# MCU.net
KiCad netlist of a schematic drawn in Altium Designer
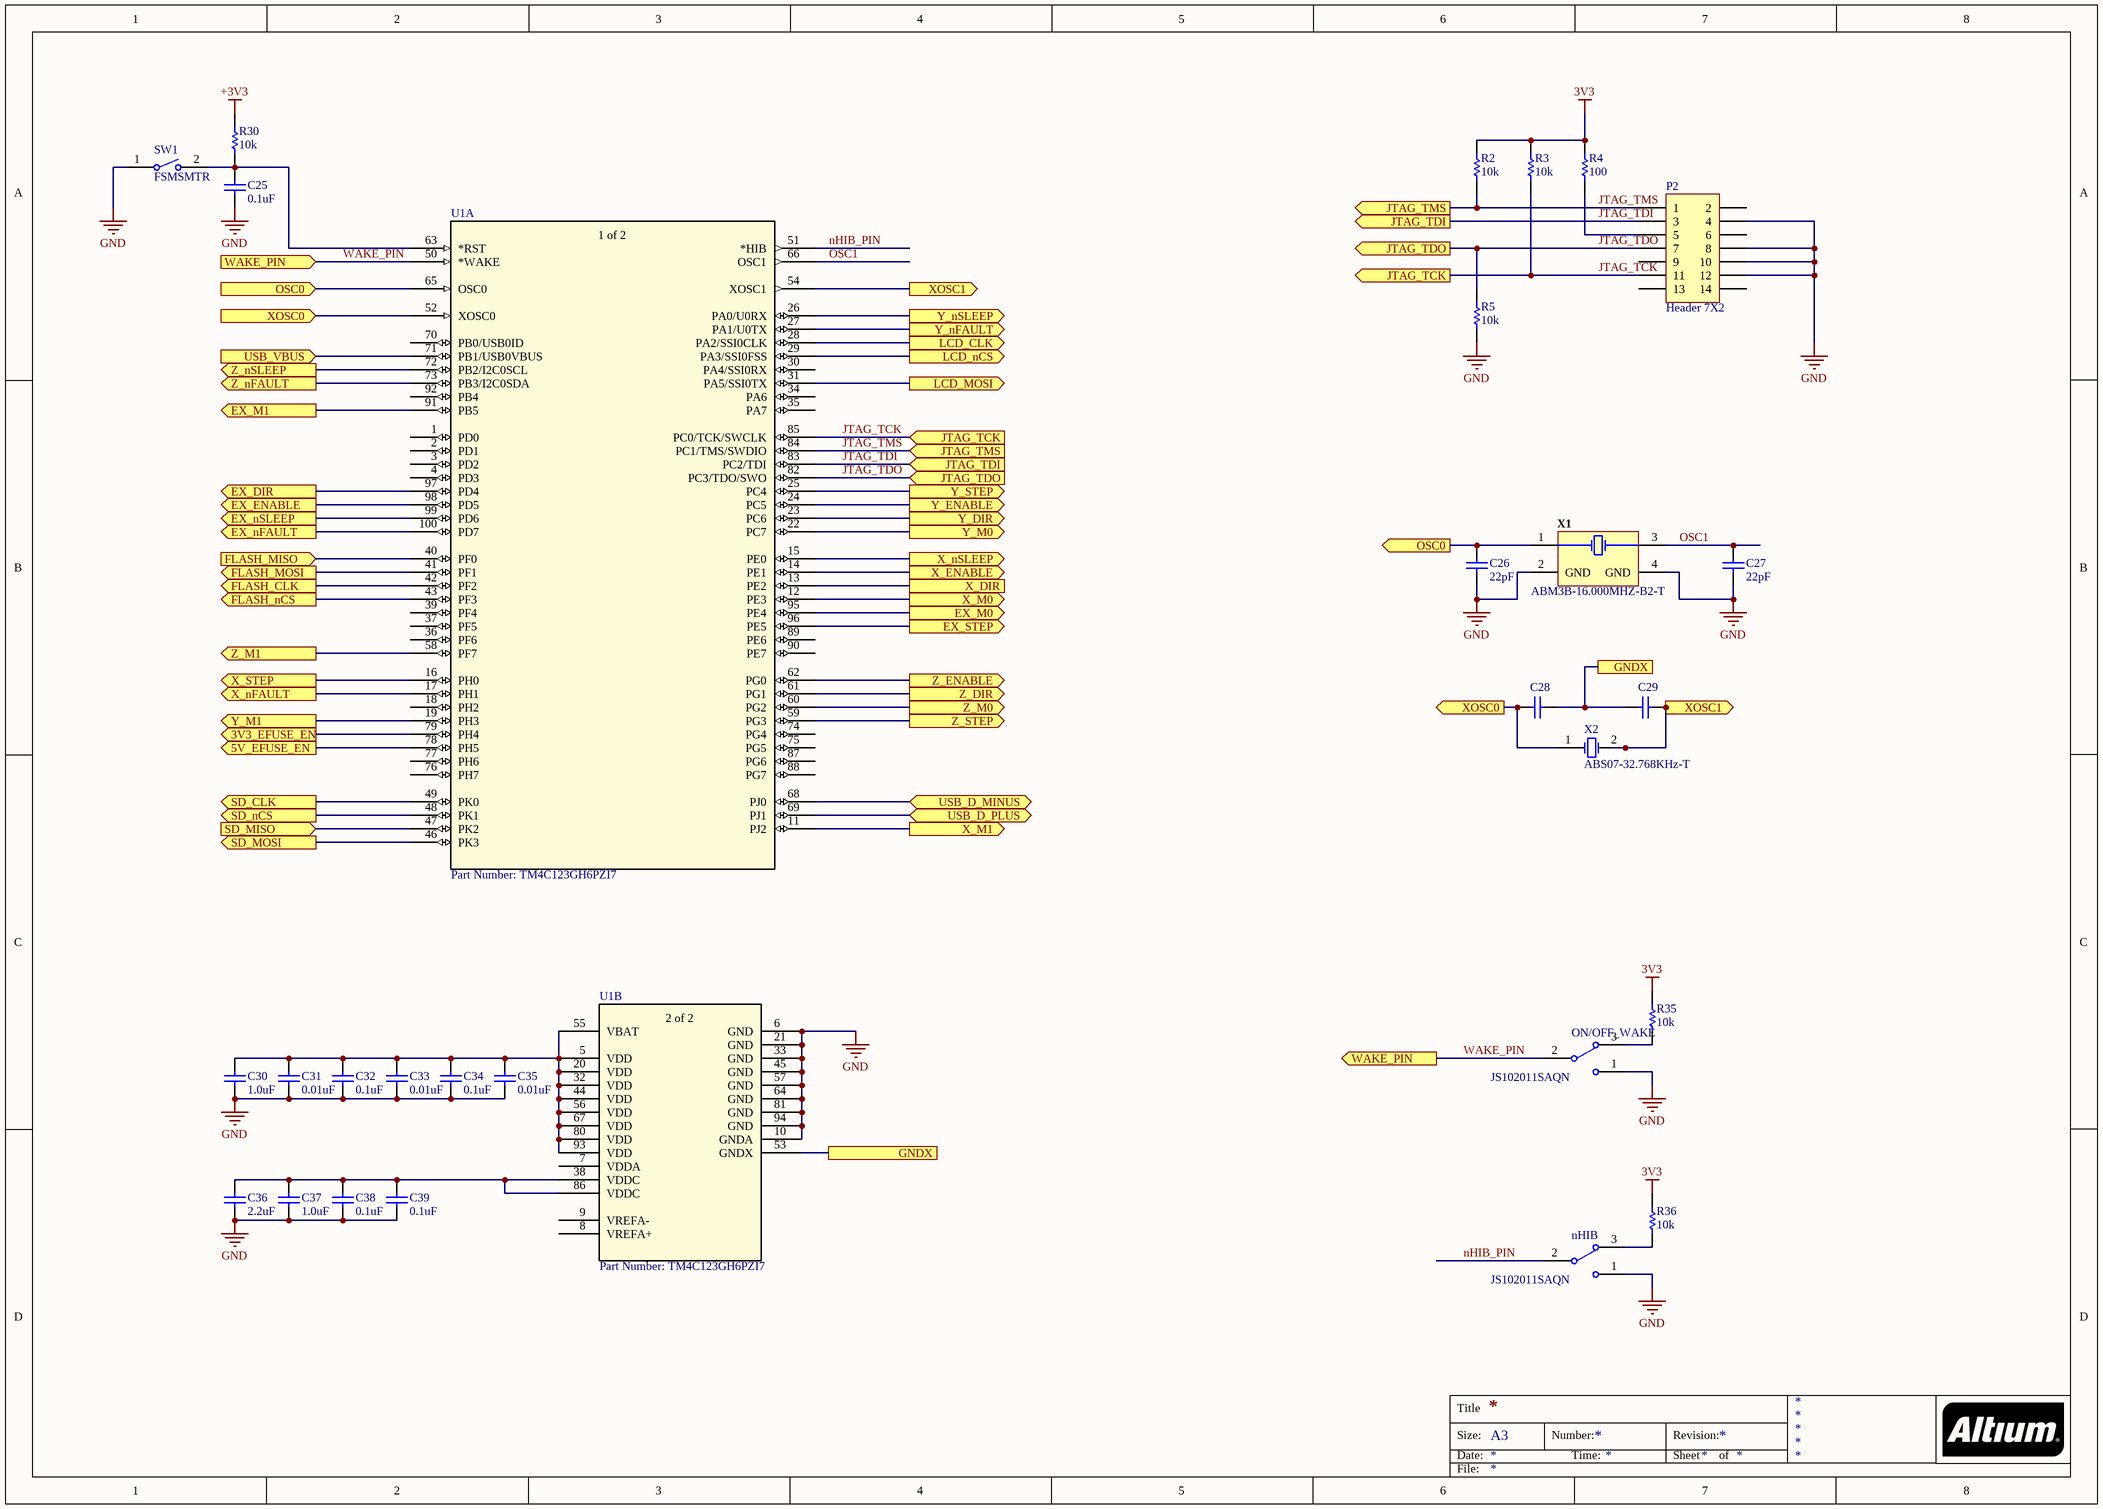
[diagram p0: MCU.SchDoc]

(export (version "E")
  (design (tool "Eeschema 10.0.6"))
  (components
    (comp (ref "C25")
      (value "0.1uF")
      (footprint "CAPC1608X90X35ML10T15")
      (description "Chip Capacitor, 0.1 uF, +/- 10%, 50 V, -55 to 125 degC, 0603 (1608 Metric), RoHS, Tape and Reel")
      (fields (field (name "TOLERANCE") "10%") (field (name "VOLTAGE") "50V"))
      (libsource (lib "Altium Content Vault") (part "CAP-NP-2"))
    )
    (comp (ref "C26")
      (value "22pF")
      (footprint "CAPC1608X90X35ML10T15")
      (fields (field (name "PART NUMBER") "GRM1885C1H120JA01D") (field (name "MANUFACTURER") "Murata"))
      (libsource (lib "Altium Content Vault") (part "CAP"))
    )
    (comp (ref "C27")
      (value "22pF")
      (footprint "CAPC1608X90X35ML10T15")
      (fields (field (name "PART NUMBER") "GRM1885C1H120JA01D") (field (name "MANUFACTURER") "Murata"))
      (libsource (lib "Altium Content Vault") (part "CAP"))
    )
    (comp (ref "C28")
      (value "GRM1885C1H120JA01D")
      (footprint "CAPC1608X90X35ML10T15")
      (fields (field (name "MANUFACTURER") "Murata"))
      (libsource (lib "Altium Content Vault") (part "CAP"))
    )
    (comp (ref "C29")
      (value "GRM1885C1H120JA01D")
      (footprint "CAPC1608X90X35ML10T15")
      (fields (field (name "MANUFACTURER") "Murata"))
      (libsource (lib "Altium Content Vault") (part "CAP"))
    )
    (comp (ref "C30")
      (value "1.0uF")
      (footprint "CAPC1608X60X35NL10T15")
      (fields (field (name "MANUFACTURER") "Murata") (field (name "PART NUMBER") "GRM185R61C105KE44J"))
      (libsource (lib "Altium Content Vault") (part "CAP"))
    )
    (comp (ref "C31")
      (value "0.01uF")
      (footprint "CAPC1608X87X35ML15T15")
      (fields (field (name "PART NUMBER") "C0603C103K4RACTU") (field (name "MANUFACTURER") "Kemet"))
      (libsource (lib "Altium Content Vault") (part "CAP"))
    )
    (comp (ref "C32")
      (value "0.1uF")
      (footprint "CAPC1608X90X35ML10T15")
      (description "Chip Capacitor, 0.1 uF, +/- 10%, 50 V, -55 to 125 degC, 0603 (1608 Metric), RoHS, Tape and Reel")
      (fields (field (name "TOLERANCE") "10%") (field (name "VOLTAGE") "50V"))
      (libsource (lib "Altium Content Vault") (part "CAP-NP-2"))
    )
    (comp (ref "C33")
      (value "0.01uF")
      (footprint "CAPC1608X87X35ML15T15")
      (fields (field (name "PART NUMBER") "C0603C103K4RACTU") (field (name "MANUFACTURER") "Kemet"))
      (libsource (lib "Altium Content Vault") (part "CAP"))
    )
    (comp (ref "C34")
      (value "0.1uF")
      (footprint "CAPC1608X90X35ML10T15")
      (description "Chip Capacitor, 0.1 uF, +/- 10%, 50 V, -55 to 125 degC, 0603 (1608 Metric), RoHS, Tape and Reel")
      (fields (field (name "TOLERANCE") "10%") (field (name "VOLTAGE") "50V"))
      (libsource (lib "Altium Content Vault") (part "CAP-NP-2"))
    )
    (comp (ref "C35")
      (value "0.01uF")
      (footprint "CAPC1608X87X35ML15T15")
      (fields (field (name "PART NUMBER") "C0603C103K4RACTU") (field (name "MANUFACTURER") "Kemet"))
      (libsource (lib "Altium Content Vault") (part "CAP"))
    )
    (comp (ref "C36")
      (value "2.2uF")
      (footprint "CAPC1608X90X35ML10T15")
      (fields (field (name "MANUFACTURER") "Murata") (field (name "PART NUMBER") "GRM188R71A225KE15D"))
      (libsource (lib "Altium Content Vault") (part "CAP"))
    )
    (comp (ref "C37")
      (value "1.0uF")
      (footprint "CAPC1608X60X35NL10T15")
      (fields (field (name "MANUFACTURER") "Murata") (field (name "PART NUMBER") "GRM185R61C105KE44J"))
      (libsource (lib "Altium Content Vault") (part "CAP"))
    )
    (comp (ref "C38")
      (value "0.1uF")
      (footprint "CAPC1608X90X35ML10T15")
      (description "Chip Capacitor, 0.1 uF, +/- 10%, 50 V, -55 to 125 degC, 0603 (1608 Metric), RoHS, Tape and Reel")
      (fields (field (name "TOLERANCE") "10%") (field (name "VOLTAGE") "50V"))
      (libsource (lib "Altium Content Vault") (part "CAP-NP-2"))
    )
    (comp (ref "C39")
      (value "0.1uF")
      (footprint "CAPC1608X90X35ML10T15")
      (description "Chip Capacitor, 0.1 uF, +/- 10%, 50 V, -55 to 125 degC, 0603 (1608 Metric), RoHS, Tape and Reel")
      (fields (field (name "TOLERANCE") "10%") (field (name "VOLTAGE") "50V"))
      (libsource (lib "Altium Content Vault") (part "CAP-NP-2"))
    )
    (comp (ref "nHIB")
      (value "JS102011SAQN")
      (footprint "CKCP-JS102011SAQN-3_V")
      (description "Sub-Miniature Slide Switch, SPDT, -40 to 85 degC, 3-Pin SMD, RoHS, Tape and Reel")
      (fields (field (name "MANUFACTURER") "C&K Components"))
      (libsource (lib "Altium Content Vault") (part "SW-SPDT-3"))
    )
    (comp (ref "ON/OFF_WAKE")
      (value "JS102011SAQN")
      (footprint "CKCP-JS102011SAQN-3_V")
      (description "Sub-Miniature Slide Switch, SPDT, -40 to 85 degC, 3-Pin SMD, RoHS, Tape and Reel")
      (fields (field (name "MANUFACTURER") "C&K Components"))
      (libsource (lib "Altium Content Vault") (part "SW-SPDT-3"))
    )
    (comp (ref "P2")
      (value "Header 7X2")
      (footprint "HDR2X7")
      (description "Header, 7-Pin, Dual row")
      (fields (field (name "PUBLISHER") "Altium Limited"))
      (libsource (lib "Miscellaneous Connectors") (part "Header 7X2"))
    )
    (comp (ref "R2")
      (value "10k")
      (footprint "RESC1608X55X30LL15T15")
      (fields (field (name "PART NUMBER") "ERJ-3EKF1002V") (field (name "MANUFACTURER") "Panasonic"))
      (libsource (lib "Altium Content Vault") (part "RES"))
    )
    (comp (ref "R3")
      (value "10k")
      (footprint "RESC1608X55X30LL15T15")
      (fields (field (name "PART NUMBER") "ERJ-3EKF1002V") (field (name "MANUFACTURER") "Panasonic"))
      (libsource (lib "Altium Content Vault") (part "RES"))
    )
    (comp (ref "R4")
      (value "100")
      (footprint "RESC1608X55X30LL15T15")
      (fields (field (name "PART NUMBER") "ERJ-3EKF1002V") (field (name "MANUFACTURER") "Panasonic"))
      (libsource (lib "Altium Content Vault") (part "RES"))
    )
    (comp (ref "R5")
      (value "10k")
      (footprint "RESC1608X55X30LL15T15")
      (fields (field (name "PART NUMBER") "ERJ-3EKF1002V") (field (name "MANUFACTURER") "Panasonic"))
      (libsource (lib "Altium Content Vault") (part "RES"))
    )
    (comp (ref "R30")
      (value "10k")
      (footprint "RESC1608X55X30LL15T15")
      (fields (field (name "PART NUMBER") "ERJ-3EKF1002V") (field (name "MANUFACTURER") "Panasonic"))
      (libsource (lib "Altium Content Vault") (part "RES"))
    )
    (comp (ref "R35")
      (value "10k")
      (footprint "RESC1608X55X30LL15T15")
      (fields (field (name "PART NUMBER") "ERJ-3EKF1002V") (field (name "MANUFACTURER") "Panasonic"))
      (libsource (lib "Altium Content Vault") (part "RES"))
    )
    (comp (ref "R36")
      (value "10k")
      (footprint "RESC1608X55X30LL15T15")
      (fields (field (name "PART NUMBER") "ERJ-3EKF1002V") (field (name "MANUFACTURER") "Panasonic"))
      (libsource (lib "Altium Content Vault") (part "RES"))
    )
    (comp (ref "SW1")
      (value "FSMSMTR")
      (footprint "TECO-FSMSMTR_V")
      (description "FSMSM Push Button Switch, 50 mA, -35 to 85 degC, 2-Pin SMD, RoHS, Tape and Reel")
      (fields (field (name "MANUFACTURER") "TE Connectivity"))
      (libsource (lib "Altium Content Vault") (part "SW-SPST-2_C"))
    )
    (comp (ref "U1")
      (value "Part Number: TM4C123GH6PZI7")
      (footprint "PZ100")
      (description "No Description Available")
      (fields
        (field (name "MANUFACTURER_PART_NUMBER") "TM4C123GH6PZI7")
        (field (name "COPYRIGHT") "Copyright (C) 2018 Accelerated Designs. All rights reserved")
      )
      (libsource (lib "Capstone_IFFF") (part "TM4C123GH6PZI7"))
    )
    (comp (ref "X1")
      (value "ABM3B-16.000MHZ-B2-T")
      (footprint "ABRA-ABM3B-4_V")
      (description "Ceramic SMD Crystal, 16 MHz, +/- 20 ppm, 50 Ohm, -20 to 70 degC, 4-Pin SMD, RoHS, Tape and Reel")
      (fields (field (name "TOLERANCE") "30%"))
      (libsource (lib "Altium Content Vault") (part "XTAL-1-3-4"))
    )
    (comp (ref "X2")
      (value "ABS07-32.768KHz-T")
      (footprint "ABRA-ABS07-2_V")
      (description "Crystal, 32.768 kHz, 12.5 pF, -40 to 85 degC, SMD Low Profile 3.2 x 1.5 x 0.9 mm, Tape and Reel")
      (fields (field (name "MANUFACTURER") "Abracon"))
      (libsource (lib "Altium Content Vault") (part "ABRA-ABS07-2"))
    )
  )
  (nets
    (net (code "1") (name "+3V3") (class "Default")
      (node (ref "R30") (pin "2") (pinfunction "2_2") (pintype "passive"))
    )
    (net (code "2") (name "/3V3_EFUSE_EN") (class "Default")
      (node (ref "U1") (pin "79") (pinfunction "PH4_79") (pintype "bidirectional"))
    )
    (net (code "3") (name "/5V_EFUSE_EN") (class "Default")
      (node (ref "U1") (pin "78") (pinfunction "PH5_78") (pintype "bidirectional"))
    )
    (net (code "4") (name "/EX_DIR") (class "Default")
      (node (ref "U1") (pin "97") (pinfunction "PD4_97") (pintype "bidirectional"))
    )
    (net (code "5") (name "/EX_ENABLE") (class "Default")
      (node (ref "U1") (pin "98") (pinfunction "PD5_98") (pintype "bidirectional"))
    )
    (net (code "6") (name "/EX_M0") (class "Default")
      (node (ref "U1") (pin "95") (pinfunction "PE4_95") (pintype "bidirectional"))
    )
    (net (code "7") (name "/EX_M1") (class "Default")
      (node (ref "U1") (pin "91") (pinfunction "PB5_91") (pintype "bidirectional"))
    )
    (net (code "8") (name "/EX_STEP") (class "Default")
      (node (ref "U1") (pin "96") (pinfunction "PE5_96") (pintype "bidirectional"))
    )
    (net (code "9") (name "/EX_nFAULT") (class "Default")
      (node (ref "U1") (pin "100") (pinfunction "PD7_100") (pintype "bidirectional"))
    )
    (net (code "10") (name "/EX_nSLEEP") (class "Default")
      (node (ref "U1") (pin "99") (pinfunction "PD6_99") (pintype "bidirectional"))
    )
    (net (code "11") (name "/FLASH_CLK") (class "Default")
      (node (ref "U1") (pin "42") (pinfunction "PF2_42") (pintype "bidirectional"))
    )
    (net (code "12") (name "/FLASH_MISO") (class "Default")
      (node (ref "U1") (pin "40") (pinfunction "PF0_40") (pintype "bidirectional"))
    )
    (net (code "13") (name "/FLASH_MOSI") (class "Default")
      (node (ref "U1") (pin "41") (pinfunction "PF1_41") (pintype "bidirectional"))
    )
    (net (code "14") (name "/FLASH_nCS") (class "Default")
      (node (ref "U1") (pin "43") (pinfunction "PF3_43") (pintype "bidirectional"))
    )
    (net (code "15") (name "/GNDX") (class "Default")
      (node (ref "C28") (pin "2") (pinfunction "2_2") (pintype "passive"))
      (node (ref "C29") (pin "1") (pinfunction "1_1") (pintype "passive"))
      (node (ref "U1") (pin "53") (pinfunction "GNDX_53") (pintype "power_in"))
    )
    (net (code "16") (name "/JTAG_TCK") (class "Default")
      (node (ref "P2") (pin "11") (pinfunction "11_11") (pintype "passive"))
      (node (ref "R3") (pin "1") (pinfunction "1_1") (pintype "passive"))
      (node (ref "U1") (pin "85") (pinfunction "PC0/TCK/SWCLK_85") (pintype "bidirectional"))
    )
    (net (code "17") (name "/JTAG_TDI") (class "Default")
      (node (ref "P2") (pin "3") (pinfunction "3_3") (pintype "passive"))
      (node (ref "U1") (pin "83") (pinfunction "PC2/TDI_83") (pintype "bidirectional"))
    )
    (net (code "18") (name "/JTAG_TDO") (class "Default")
      (node (ref "P2") (pin "7") (pinfunction "7_7") (pintype "passive"))
      (node (ref "R5") (pin "2") (pinfunction "2_2") (pintype "passive"))
      (node (ref "U1") (pin "82") (pinfunction "PC3/TDO/SWO_82") (pintype "bidirectional"))
    )
    (net (code "19") (name "/JTAG_TMS") (class "Default")
      (node (ref "P2") (pin "1") (pinfunction "1_1") (pintype "passive"))
      (node (ref "R2") (pin "1") (pinfunction "1_1") (pintype "passive"))
      (node (ref "U1") (pin "84") (pinfunction "PC1/TMS/SWDIO_84") (pintype "bidirectional"))
    )
    (net (code "20") (name "/LCD_CLK") (class "Default")
      (node (ref "U1") (pin "28") (pinfunction "PA2/SSI0CLK_28") (pintype "bidirectional"))
    )
    (net (code "21") (name "/LCD_MOSI") (class "Default")
      (node (ref "U1") (pin "31") (pinfunction "PA5/SSI0TX_31") (pintype "bidirectional"))
    )
    (net (code "22") (name "/LCD_nCS") (class "Default")
      (node (ref "U1") (pin "29") (pinfunction "PA3/SSI0FSS_29") (pintype "bidirectional"))
    )
    (net (code "23") (name "/OSC0") (class "Default")
      (node (ref "C26") (pin "2") (pinfunction "2_2") (pintype "passive"))
      (node (ref "U1") (pin "65") (pinfunction "OSC0_65") (pintype "input"))
      (node (ref "X1") (pin "1") (pinfunction "X1_1") (pintype "passive"))
    )
    (net (code "24") (name "/OSC1") (class "Default")
      (node (ref "C27") (pin "2") (pinfunction "2_2") (pintype "passive"))
      (node (ref "U1") (pin "66") (pinfunction "OSC1_66") (pintype "output"))
      (node (ref "X1") (pin "3") (pinfunction "X2_3") (pintype "passive"))
    )
    (net (code "25") (name "/SD_CLK") (class "Default")
      (node (ref "U1") (pin "49") (pinfunction "PK0_49") (pintype "bidirectional"))
    )
    (net (code "26") (name "/SD_MISO") (class "Default")
      (node (ref "U1") (pin "47") (pinfunction "PK2_47") (pintype "bidirectional"))
    )
    (net (code "27") (name "/SD_MOSI") (class "Default")
      (node (ref "U1") (pin "46") (pinfunction "PK3_46") (pintype "bidirectional"))
    )
    (net (code "28") (name "/SD_nCS") (class "Default")
      (node (ref "U1") (pin "48") (pinfunction "PK1_48") (pintype "bidirectional"))
    )
    (net (code "29") (name "/USB_D_MINUS") (class "Default")
      (node (ref "U1") (pin "68") (pinfunction "PJ0_68") (pintype "bidirectional"))
    )
    (net (code "30") (name "/USB_D_PLUS") (class "Default")
      (node (ref "U1") (pin "69") (pinfunction "PJ1_69") (pintype "bidirectional"))
    )
    (net (code "31") (name "/USB_VBUS") (class "Default")
      (node (ref "U1") (pin "71") (pinfunction "PB1/USB0VBUS_71") (pintype "bidirectional"))
    )
    (net (code "32") (name "/WAKE_PIN") (class "Default")
      (node (ref "ON/OFF_WAKE") (pin "2") (pinfunction "2_2") (pintype "passive"))
      (node (ref "U1") (pin "50") (pinfunction "*WAKE_50") (pintype "input"))
    )
    (net (code "33") (name "/XOSC0") (class "Default")
      (node (ref "C28") (pin "1") (pinfunction "1_1") (pintype "passive"))
      (node (ref "U1") (pin "52") (pinfunction "XOSC0_52") (pintype "input"))
      (node (ref "X2") (pin "1") (pinfunction "X1_1") (pintype "passive"))
    )
    (net (code "34") (name "/XOSC1") (class "Default")
      (node (ref "C29") (pin "2") (pinfunction "2_2") (pintype "passive"))
      (node (ref "U1") (pin "54") (pinfunction "XOSC1_54") (pintype "output"))
      (node (ref "X2") (pin "2") (pinfunction "X2_2") (pintype "passive"))
    )
    (net (code "35") (name "/X_DIR") (class "Default")
      (node (ref "U1") (pin "13") (pinfunction "PE2_13") (pintype "bidirectional"))
    )
    (net (code "36") (name "/X_ENABLE") (class "Default")
      (node (ref "U1") (pin "14") (pinfunction "PE1_14") (pintype "bidirectional"))
    )
    (net (code "37") (name "/X_M0") (class "Default")
      (node (ref "U1") (pin "12") (pinfunction "PE3_12") (pintype "bidirectional"))
    )
    (net (code "38") (name "/X_M1") (class "Default")
      (node (ref "U1") (pin "11") (pinfunction "PJ2_11") (pintype "bidirectional"))
    )
    (net (code "39") (name "/X_STEP") (class "Default")
      (node (ref "U1") (pin "16") (pinfunction "PH0_16") (pintype "bidirectional"))
    )
    (net (code "40") (name "/X_nFAULT") (class "Default")
      (node (ref "U1") (pin "17") (pinfunction "PH1_17") (pintype "bidirectional"))
    )
    (net (code "41") (name "/X_nSLEEP") (class "Default")
      (node (ref "U1") (pin "15") (pinfunction "PE0_15") (pintype "bidirectional"))
    )
    (net (code "42") (name "/Y_DIR") (class "Default")
      (node (ref "U1") (pin "23") (pinfunction "PC6_23") (pintype "bidirectional"))
    )
    (net (code "43") (name "/Y_ENABLE") (class "Default")
      (node (ref "U1") (pin "24") (pinfunction "PC5_24") (pintype "bidirectional"))
    )
    (net (code "44") (name "/Y_M0") (class "Default")
      (node (ref "U1") (pin "22") (pinfunction "PC7_22") (pintype "bidirectional"))
    )
    (net (code "45") (name "/Y_M1") (class "Default")
      (node (ref "U1") (pin "19") (pinfunction "PH3_19") (pintype "bidirectional"))
    )
    (net (code "46") (name "/Y_STEP") (class "Default")
      (node (ref "U1") (pin "25") (pinfunction "PC4_25") (pintype "bidirectional"))
    )
    (net (code "47") (name "/Y_nFAULT") (class "Default")
      (node (ref "U1") (pin "27") (pinfunction "PA1/U0TX_27") (pintype "bidirectional"))
    )
    (net (code "48") (name "/Y_nSLEEP") (class "Default")
      (node (ref "U1") (pin "26") (pinfunction "PA0/U0RX_26") (pintype "bidirectional"))
    )
    (net (code "49") (name "/Z_DIR") (class "Default")
      (node (ref "U1") (pin "61") (pinfunction "PG1_61") (pintype "bidirectional"))
    )
    (net (code "50") (name "/Z_ENABLE") (class "Default")
      (node (ref "U1") (pin "62") (pinfunction "PG0_62") (pintype "bidirectional"))
    )
    (net (code "51") (name "/Z_M0") (class "Default")
      (node (ref "U1") (pin "60") (pinfunction "PG2_60") (pintype "bidirectional"))
    )
    (net (code "52") (name "/Z_M1") (class "Default")
      (node (ref "U1") (pin "58") (pinfunction "PF7_58") (pintype "bidirectional"))
    )
    (net (code "53") (name "/Z_STEP") (class "Default")
      (node (ref "U1") (pin "59") (pinfunction "PG3_59") (pintype "bidirectional"))
    )
    (net (code "54") (name "/Z_nFAULT") (class "Default")
      (node (ref "U1") (pin "73") (pinfunction "PB3/I2C0SDA_73") (pintype "bidirectional"))
    )
    (net (code "55") (name "/Z_nSLEEP") (class "Default")
      (node (ref "U1") (pin "72") (pinfunction "PB2/I2C0SCL_72") (pintype "bidirectional"))
    )
    (net (code "56") (name "/nHIB_PIN") (class "Default")
      (node (ref "U1") (pin "51") (pinfunction "*HIB_51") (pintype "output"))
      (node (ref "nHIB") (pin "2") (pinfunction "2_2") (pintype "passive"))
    )
    (net (code "57") (name "3V3") (class "Default")
      (node (ref "R2") (pin "2") (pinfunction "2_2") (pintype "passive"))
      (node (ref "R3") (pin "2") (pinfunction "2_2") (pintype "passive"))
      (node (ref "R35") (pin "2") (pinfunction "2_2") (pintype "passive"))
      (node (ref "R36") (pin "2") (pinfunction "2_2") (pintype "passive"))
      (node (ref "R4") (pin "2") (pinfunction "2_2") (pintype "passive"))
    )
    (net (code "58") (name "GND") (class "Default")
      (node (ref "C25") (pin "1") (pinfunction "1_1") (pintype "passive"))
      (node (ref "C26") (pin "1") (pinfunction "1_1") (pintype "passive"))
      (node (ref "C27") (pin "1") (pinfunction "1_1") (pintype "passive"))
      (node (ref "C30") (pin "1") (pinfunction "1_1") (pintype "passive"))
      (node (ref "C31") (pin "1") (pinfunction "1_1") (pintype "passive"))
      (node (ref "C32") (pin "1") (pinfunction "1_1") (pintype "passive"))
      (node (ref "C33") (pin "1") (pinfunction "1_1") (pintype "passive"))
      (node (ref "C34") (pin "1") (pinfunction "1_1") (pintype "passive"))
      (node (ref "C35") (pin "1") (pinfunction "1_1") (pintype "passive"))
      (node (ref "C36") (pin "1") (pinfunction "1_1") (pintype "passive"))
      (node (ref "C37") (pin "1") (pinfunction "1_1") (pintype "passive"))
      (node (ref "C38") (pin "1") (pinfunction "1_1") (pintype "passive"))
      (node (ref "C39") (pin "1") (pinfunction "1_1") (pintype "passive"))
      (node (ref "ON/OFF_WAKE") (pin "1") (pinfunction "1_1") (pintype "passive"))
      (node (ref "P2") (pin "10") (pinfunction "10_10") (pintype "passive"))
      (node (ref "P2") (pin "12") (pinfunction "12_12") (pintype "passive"))
      (node (ref "P2") (pin "4") (pinfunction "4_4") (pintype "passive"))
      (node (ref "P2") (pin "8") (pinfunction "8_8") (pintype "passive"))
      (node (ref "R5") (pin "1") (pinfunction "1_1") (pintype "passive"))
      (node (ref "SW1") (pin "1") (pinfunction "1_1") (pintype "passive"))
      (node (ref "U1") (pin "10") (pinfunction "GNDA_10") (pintype "power_in"))
      (node (ref "U1") (pin "21") (pinfunction "GND_21") (pintype "power_in"))
      (node (ref "U1") (pin "33") (pinfunction "GND_33") (pintype "power_in"))
      (node (ref "U1") (pin "45") (pinfunction "GND_45") (pintype "power_in"))
      (node (ref "U1") (pin "57") (pinfunction "GND_57") (pintype "power_in"))
      (node (ref "U1") (pin "6") (pinfunction "GND_6") (pintype "power_in"))
      (node (ref "U1") (pin "64") (pinfunction "GND_64") (pintype "power_in"))
      (node (ref "U1") (pin "81") (pinfunction "GND_81") (pintype "power_in"))
      (node (ref "U1") (pin "94") (pinfunction "GND_94") (pintype "power_in"))
      (node (ref "X1") (pin "2") (pinfunction "GND_2") (pintype "power_in"))
      (node (ref "X1") (pin "4") (pinfunction "GND_4") (pintype "power_in"))
      (node (ref "nHIB") (pin "1") (pinfunction "1_1") (pintype "passive"))
    )
    (net (code "59") (name "Net-(C36-Pad2)") (class "Default")
      (node (ref "C36") (pin "2") (pinfunction "2_2") (pintype "passive"))
      (node (ref "C37") (pin "2") (pinfunction "2_2") (pintype "passive"))
      (node (ref "C38") (pin "2") (pinfunction "2_2") (pintype "passive"))
      (node (ref "C39") (pin "2") (pinfunction "2_2") (pintype "passive"))
      (node (ref "U1") (pin "38") (pinfunction "VDDC_38") (pintype "power_in"))
      (node (ref "U1") (pin "86") (pinfunction "VDDC_86") (pintype "power_in"))
    )
    (net (code "60") (name "Net-(ON/OFF_WAKE-Pad3)") (class "Default")
      (node (ref "ON/OFF_WAKE") (pin "3") (pinfunction "3_3") (pintype "passive"))
      (node (ref "R35") (pin "1") (pinfunction "1_1") (pintype "passive"))
    )
    (net (code "61") (name "Net-(P2-Pad5)") (class "Default")
      (node (ref "P2") (pin "5") (pinfunction "5_5") (pintype "passive"))
      (node (ref "R4") (pin "1") (pinfunction "1_1") (pintype "passive"))
    )
    (net (code "62") (name "Net-(R36-Pad1)") (class "Default")
      (node (ref "R36") (pin "1") (pinfunction "1_1") (pintype "passive"))
      (node (ref "nHIB") (pin "3") (pinfunction "3_3") (pintype "passive"))
    )
    (net (code "63") (name "Net-(U1A-*RST)") (class "Default")
      (node (ref "C25") (pin "2") (pinfunction "2_2") (pintype "passive"))
      (node (ref "R30") (pin "1") (pinfunction "1_1") (pintype "passive"))
      (node (ref "SW1") (pin "2") (pinfunction "2_2") (pintype "passive"))
      (node (ref "U1") (pin "63") (pinfunction "*RST_63") (pintype "input"))
    )
    (net (code "64") (name "Net-(U1B-VBAT)") (class "Default")
      (node (ref "C30") (pin "2") (pinfunction "2_2") (pintype "passive"))
      (node (ref "C31") (pin "2") (pinfunction "2_2") (pintype "passive"))
      (node (ref "C32") (pin "2") (pinfunction "2_2") (pintype "passive"))
      (node (ref "C33") (pin "2") (pinfunction "2_2") (pintype "passive"))
      (node (ref "C34") (pin "2") (pinfunction "2_2") (pintype "passive"))
      (node (ref "C35") (pin "2") (pinfunction "2_2") (pintype "passive"))
      (node (ref "U1") (pin "20") (pinfunction "VDD_20") (pintype "power_in"))
      (node (ref "U1") (pin "32") (pinfunction "VDD_32") (pintype "power_in"))
      (node (ref "U1") (pin "44") (pinfunction "VDD_44") (pintype "power_in"))
      (node (ref "U1") (pin "5") (pinfunction "VDD_5") (pintype "power_in"))
      (node (ref "U1") (pin "55") (pinfunction "VBAT_55") (pintype "power_in"))
      (node (ref "U1") (pin "56") (pinfunction "VDD_56") (pintype "power_in"))
      (node (ref "U1") (pin "67") (pinfunction "VDD_67") (pintype "power_in"))
      (node (ref "U1") (pin "80") (pinfunction "VDD_80") (pintype "power_in"))
      (node (ref "U1") (pin "93") (pinfunction "VDD_93") (pintype "power_in"))
    )
    (net (code "65") (name "unconnected-(P2-Pad2)") (class "Default")
      (node (ref "P2") (pin "2") (pinfunction "2_2") (pintype "passive"))
    )
    (net (code "66") (name "unconnected-(P2-Pad6)") (class "Default")
      (node (ref "P2") (pin "6") (pinfunction "6_6") (pintype "passive"))
    )
    (net (code "67") (name "unconnected-(P2-Pad9)") (class "Default")
      (node (ref "P2") (pin "9") (pinfunction "9_9") (pintype "passive"))
    )
    (net (code "68") (name "unconnected-(P2-Pad13)") (class "Default")
      (node (ref "P2") (pin "13") (pinfunction "13_13") (pintype "passive"))
    )
    (net (code "69") (name "unconnected-(P2-Pad14)") (class "Default")
      (node (ref "P2") (pin "14") (pinfunction "14_14") (pintype "passive"))
    )
    (net (code "70") (name "unconnected-(U1A-PA4{slash}SSI0RX-Pad30)") (class "Default")
      (node (ref "U1") (pin "30") (pinfunction "PA4/SSI0RX_30") (pintype "bidirectional"))
    )
    (net (code "71") (name "unconnected-(U1A-PA6-Pad34)") (class "Default")
      (node (ref "U1") (pin "34") (pinfunction "PA6_34") (pintype "bidirectional"))
    )
    (net (code "72") (name "unconnected-(U1A-PA7-Pad35)") (class "Default")
      (node (ref "U1") (pin "35") (pinfunction "PA7_35") (pintype "bidirectional"))
    )
    (net (code "73") (name "unconnected-(U1A-PB0{slash}USB0ID-Pad70)") (class "Default")
      (node (ref "U1") (pin "70") (pinfunction "PB0/USB0ID_70") (pintype "bidirectional"))
    )
    (net (code "74") (name "unconnected-(U1A-PB4-Pad92)") (class "Default")
      (node (ref "U1") (pin "92") (pinfunction "PB4_92") (pintype "bidirectional"))
    )
    (net (code "75") (name "unconnected-(U1A-PD0-Pad1)") (class "Default")
      (node (ref "U1") (pin "1") (pinfunction "PD0_1") (pintype "bidirectional"))
    )
    (net (code "76") (name "unconnected-(U1A-PD1-Pad2)") (class "Default")
      (node (ref "U1") (pin "2") (pinfunction "PD1_2") (pintype "bidirectional"))
    )
    (net (code "77") (name "unconnected-(U1A-PD2-Pad3)") (class "Default")
      (node (ref "U1") (pin "3") (pinfunction "PD2_3") (pintype "bidirectional"))
    )
    (net (code "78") (name "unconnected-(U1A-PD3-Pad4)") (class "Default")
      (node (ref "U1") (pin "4") (pinfunction "PD3_4") (pintype "bidirectional"))
    )
    (net (code "79") (name "unconnected-(U1A-PE6-Pad89)") (class "Default")
      (node (ref "U1") (pin "89") (pinfunction "PE6_89") (pintype "bidirectional"))
    )
    (net (code "80") (name "unconnected-(U1A-PE7-Pad90)") (class "Default")
      (node (ref "U1") (pin "90") (pinfunction "PE7_90") (pintype "bidirectional"))
    )
    (net (code "81") (name "unconnected-(U1A-PF4-Pad39)") (class "Default")
      (node (ref "U1") (pin "39") (pinfunction "PF4_39") (pintype "bidirectional"))
    )
    (net (code "82") (name "unconnected-(U1A-PF5-Pad37)") (class "Default")
      (node (ref "U1") (pin "37") (pinfunction "PF5_37") (pintype "bidirectional"))
    )
    (net (code "83") (name "unconnected-(U1A-PF6-Pad36)") (class "Default")
      (node (ref "U1") (pin "36") (pinfunction "PF6_36") (pintype "bidirectional"))
    )
    (net (code "84") (name "unconnected-(U1A-PG4-Pad74)") (class "Default")
      (node (ref "U1") (pin "74") (pinfunction "PG4_74") (pintype "bidirectional"))
    )
    (net (code "85") (name "unconnected-(U1A-PG5-Pad75)") (class "Default")
      (node (ref "U1") (pin "75") (pinfunction "PG5_75") (pintype "bidirectional"))
    )
    (net (code "86") (name "unconnected-(U1A-PG6-Pad87)") (class "Default")
      (node (ref "U1") (pin "87") (pinfunction "PG6_87") (pintype "bidirectional"))
    )
    (net (code "87") (name "unconnected-(U1A-PG7-Pad88)") (class "Default")
      (node (ref "U1") (pin "88") (pinfunction "PG7_88") (pintype "bidirectional"))
    )
    (net (code "88") (name "unconnected-(U1A-PH2-Pad18)") (class "Default")
      (node (ref "U1") (pin "18") (pinfunction "PH2_18") (pintype "bidirectional"))
    )
    (net (code "89") (name "unconnected-(U1A-PH6-Pad77)") (class "Default")
      (node (ref "U1") (pin "77") (pinfunction "PH6_77") (pintype "bidirectional"))
    )
    (net (code "90") (name "unconnected-(U1A-PH7-Pad76)") (class "Default")
      (node (ref "U1") (pin "76") (pinfunction "PH7_76") (pintype "bidirectional"))
    )
    (net (code "91") (name "unconnected-(U1B-VDDA-Pad7)") (class "Default")
      (node (ref "U1") (pin "7") (pinfunction "VDDA_7") (pintype "power_in"))
    )
    (net (code "92") (name "unconnected-(U1B-VREFA+-Pad8)") (class "Default")
      (node (ref "U1") (pin "8") (pinfunction "VREFA+_8") (pintype "power_in"))
    )
    (net (code "93") (name "unconnected-(U1B-VREFA--Pad9)") (class "Default")
      (node (ref "U1") (pin "9") (pinfunction "VREFA-_9") (pintype "power_in"))
    )
  )
)
